# PAGE112.net
KiCad netlist of a schematic drawn in Altium Designer
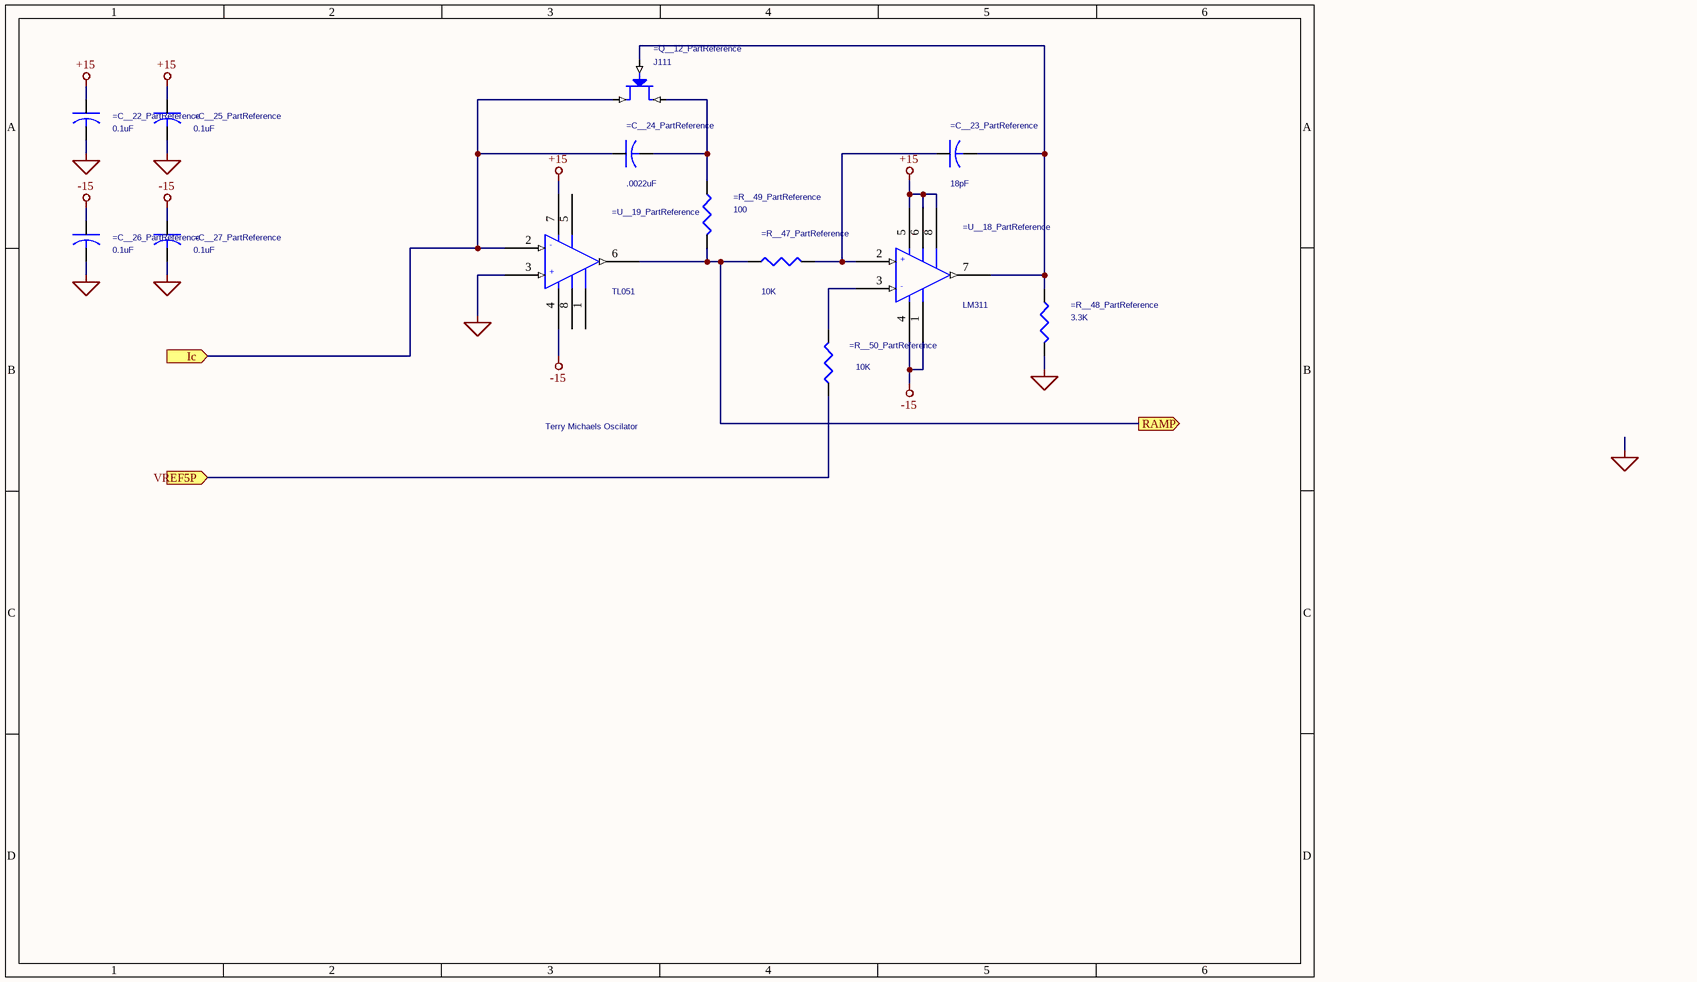
[diagram p0: PAGE112.SchDoc]

(export (version "E")
  (design (tool "Eeschema 10.0.6"))
  (components
    (comp (ref "=C__22_PartReference")
      (value "0.1uF")
      (fields (field (name "PART NO") "80-C410C104M5U"))
      (libsource (lib "*") (part "CAP_Dup1"))
    )
    (comp (ref "=C__23_PartReference")
      (value "18pF")
      (fields (field (name "PART NO") "140-50N2-180J"))
      (libsource (lib "*") (part "CAP_Dup1"))
    )
    (comp (ref "=C__24_PartReference")
      (value ".0022uF")
      (fields (field (name "PART NO") "23PS310"))
      (libsource (lib "*") (part "CAP_Dup1"))
    )
    (comp (ref "=C__25_PartReference")
      (value "0.1uF")
      (fields (field (name "PART NO") "80-C410C104M5U"))
      (libsource (lib "*") (part "CAP_Dup1"))
    )
    (comp (ref "=C__26_PartReference")
      (value "0.1uF")
      (fields (field (name "PART NO") "80-C410C104M5U"))
      (libsource (lib "*") (part "CAP_Dup1"))
    )
    (comp (ref "=C__27_PartReference")
      (value "0.1uF")
      (fields (field (name "PART NO") "80-C410C104M5U"))
      (libsource (lib "*") (part "CAP_Dup1"))
    )
    (comp (ref "=Q__12_PartReference") (value "J111") (libsource (lib "*") (part "JFET N")))
    (comp (ref "=R__47_PartReference")
      (value "10K")
      (fields (field (name "PART NO") "271-10K"))
      (libsource (lib "*") (part "R_Dup1"))
    )
    (comp (ref "=R__48_PartReference")
      (value "3.3K")
      (fields (field (name "PART NO") "271-3.3K"))
      (libsource (lib "*") (part "R_Dup1"))
    )
    (comp (ref "=R__49_PartReference")
      (value "100")
      (fields (field (name "PART NO") "271-100"))
      (libsource (lib "*") (part "R_Dup1"))
    )
    (comp (ref "=R__50_PartReference")
      (value "10K")
      (fields (field (name "PART NO") "271-10K"))
      (libsource (lib "*") (part "R_Dup1"))
    )
    (comp (ref "=U__18_PartReference")
      (value "LM311")
      (fields (field (name "PART NO") "511-LM311"))
      (libsource (lib "*") (part "LM311"))
    )
    (comp (ref "=U__19_PartReference") (value "TL051") (libsource (lib "*") (part "GENERIC OPAMP")))
  )
  (nets
    (net (code "1") (name "+15") (class "Default")
      (node (ref "=C__22_PartReference") (pin "1") (pinfunction "1_1") (pintype "passive"))
      (node (ref "=C__25_PartReference") (pin "1") (pinfunction "1_1") (pintype "passive"))
      (node (ref "=U__18_PartReference") (pin "5") (pinfunction "BALANCE_5") (pintype "passive"))
      (node (ref "=U__18_PartReference") (pin "6") (pinfunction "BAL/STROBE_6") (pintype "passive"))
      (node (ref "=U__18_PartReference") (pin "8") (pinfunction "V+_8") (pintype "passive"))
      (node (ref "=U__19_PartReference") (pin "7") (pinfunction "V+_7") (pintype "passive"))
    )
    (net (code "2") (name "-15") (class "Default")
      (node (ref "=C__26_PartReference") (pin "1") (pinfunction "1_1") (pintype "passive"))
      (node (ref "=C__27_PartReference") (pin "1") (pinfunction "1_1") (pintype "passive"))
      (node (ref "=U__18_PartReference") (pin "1") (pinfunction "GND_1") (pintype "passive"))
      (node (ref "=U__18_PartReference") (pin "4") (pinfunction "V-_4") (pintype "passive"))
      (node (ref "=U__19_PartReference") (pin "4") (pinfunction "V-_4") (pintype "passive"))
    )
    (net (code "3") (name "/Ic") (class "Default")
      (node (ref "=C__24_PartReference") (pin "1") (pinfunction "1_1") (pintype "passive"))
      (node (ref "=Q__12_PartReference") (pin "SOURCE") (pinfunction "SOURCE_SOURCE") (pintype "input"))
      (node (ref "=U__19_PartReference") (pin "2") (pinfunction "-IN_2") (pintype "input"))
    )
    (net (code "4") (name "/RAMP") (class "Default")
      (node (ref "=R__47_PartReference") (pin "1") (pinfunction "1_1") (pintype "passive"))
      (node (ref "=R__49_PartReference") (pin "2") (pinfunction "2_2") (pintype "passive"))
      (node (ref "=U__19_PartReference") (pin "6") (pinfunction "OUT_6") (pintype "output"))
    )
    (net (code "5") (name "/VREF5P") (class "Default")
      (node (ref "=R__50_PartReference") (pin "1") (pinfunction "1_1") (pintype "passive"))
    )
    (net (code "6") (name "GND") (class "Default")
      (node (ref "=C__22_PartReference") (pin "2") (pinfunction "2_2") (pintype "passive"))
      (node (ref "=C__25_PartReference") (pin "2") (pinfunction "2_2") (pintype "passive"))
      (node (ref "=C__26_PartReference") (pin "2") (pinfunction "2_2") (pintype "passive"))
      (node (ref "=C__27_PartReference") (pin "2") (pinfunction "2_2") (pintype "passive"))
      (node (ref "=R__48_PartReference") (pin "2") (pinfunction "2_2") (pintype "passive"))
      (node (ref "=U__19_PartReference") (pin "3") (pinfunction "+IN_3") (pintype "input"))
    )
    (net (code "8") (name "Net-(=C__24_PartReference-Pad2)") (class "Default")
      (node (ref "=C__24_PartReference") (pin "2") (pinfunction "2_2") (pintype "passive"))
      (node (ref "=Q__12_PartReference") (pin "DRAIN") (pinfunction "DRAIN_DRAIN") (pintype "input"))
      (node (ref "=R__49_PartReference") (pin "1") (pinfunction "1_1") (pintype "passive"))
    )
    (net (code "9") (name "Net-(=U__18_PartReference-+IN)") (class "Default")
      (node (ref "=C__23_PartReference") (pin "1") (pinfunction "1_1") (pintype "passive"))
      (node (ref "=R__47_PartReference") (pin "2") (pinfunction "2_2") (pintype "passive"))
      (node (ref "=U__18_PartReference") (pin "2") (pinfunction "+IN_2") (pintype "input"))
    )
    (net (code "10") (name "Net-(=U__18_PartReference--IN)") (class "Default")
      (node (ref "=R__50_PartReference") (pin "2") (pinfunction "2_2") (pintype "passive"))
      (node (ref "=U__18_PartReference") (pin "3") (pinfunction "-IN_3") (pintype "input"))
    )
    (net (code "11") (name "Net-(=U__18_PartReference-OUT)") (class "Default")
      (node (ref "=C__23_PartReference") (pin "2") (pinfunction "2_2") (pintype "passive"))
      (node (ref "=Q__12_PartReference") (pin "GATE") (pinfunction "GATE_GATE") (pintype "input"))
      (node (ref "=R__48_PartReference") (pin "1") (pinfunction "1_1") (pintype "passive"))
      (node (ref "=U__18_PartReference") (pin "7") (pinfunction "OUT_7") (pintype "output"))
    )
    (net (code "12") (name "unconnected-(=U__19_PartReference-COMP1-Pad5)") (class "Default")
      (node (ref "=U__19_PartReference") (pin "5") (pinfunction "COMP1_5") (pintype "passive"))
    )
    (net (code "13") (name "unconnected-(=U__19_PartReference-COMP2-Pad8)") (class "Default")
      (node (ref "=U__19_PartReference") (pin "8") (pinfunction "COMP2_8") (pintype "passive"))
    )
    (net (code "14") (name "unconnected-(=U__19_PartReference-COMP3-Pad1)") (class "Default")
      (node (ref "=U__19_PartReference") (pin "1") (pinfunction "COMP3_1") (pintype "passive"))
    )
  )
)
